# 18_DDR3_TOP.net
KiCad netlist of a schematic drawn in Altium Designer
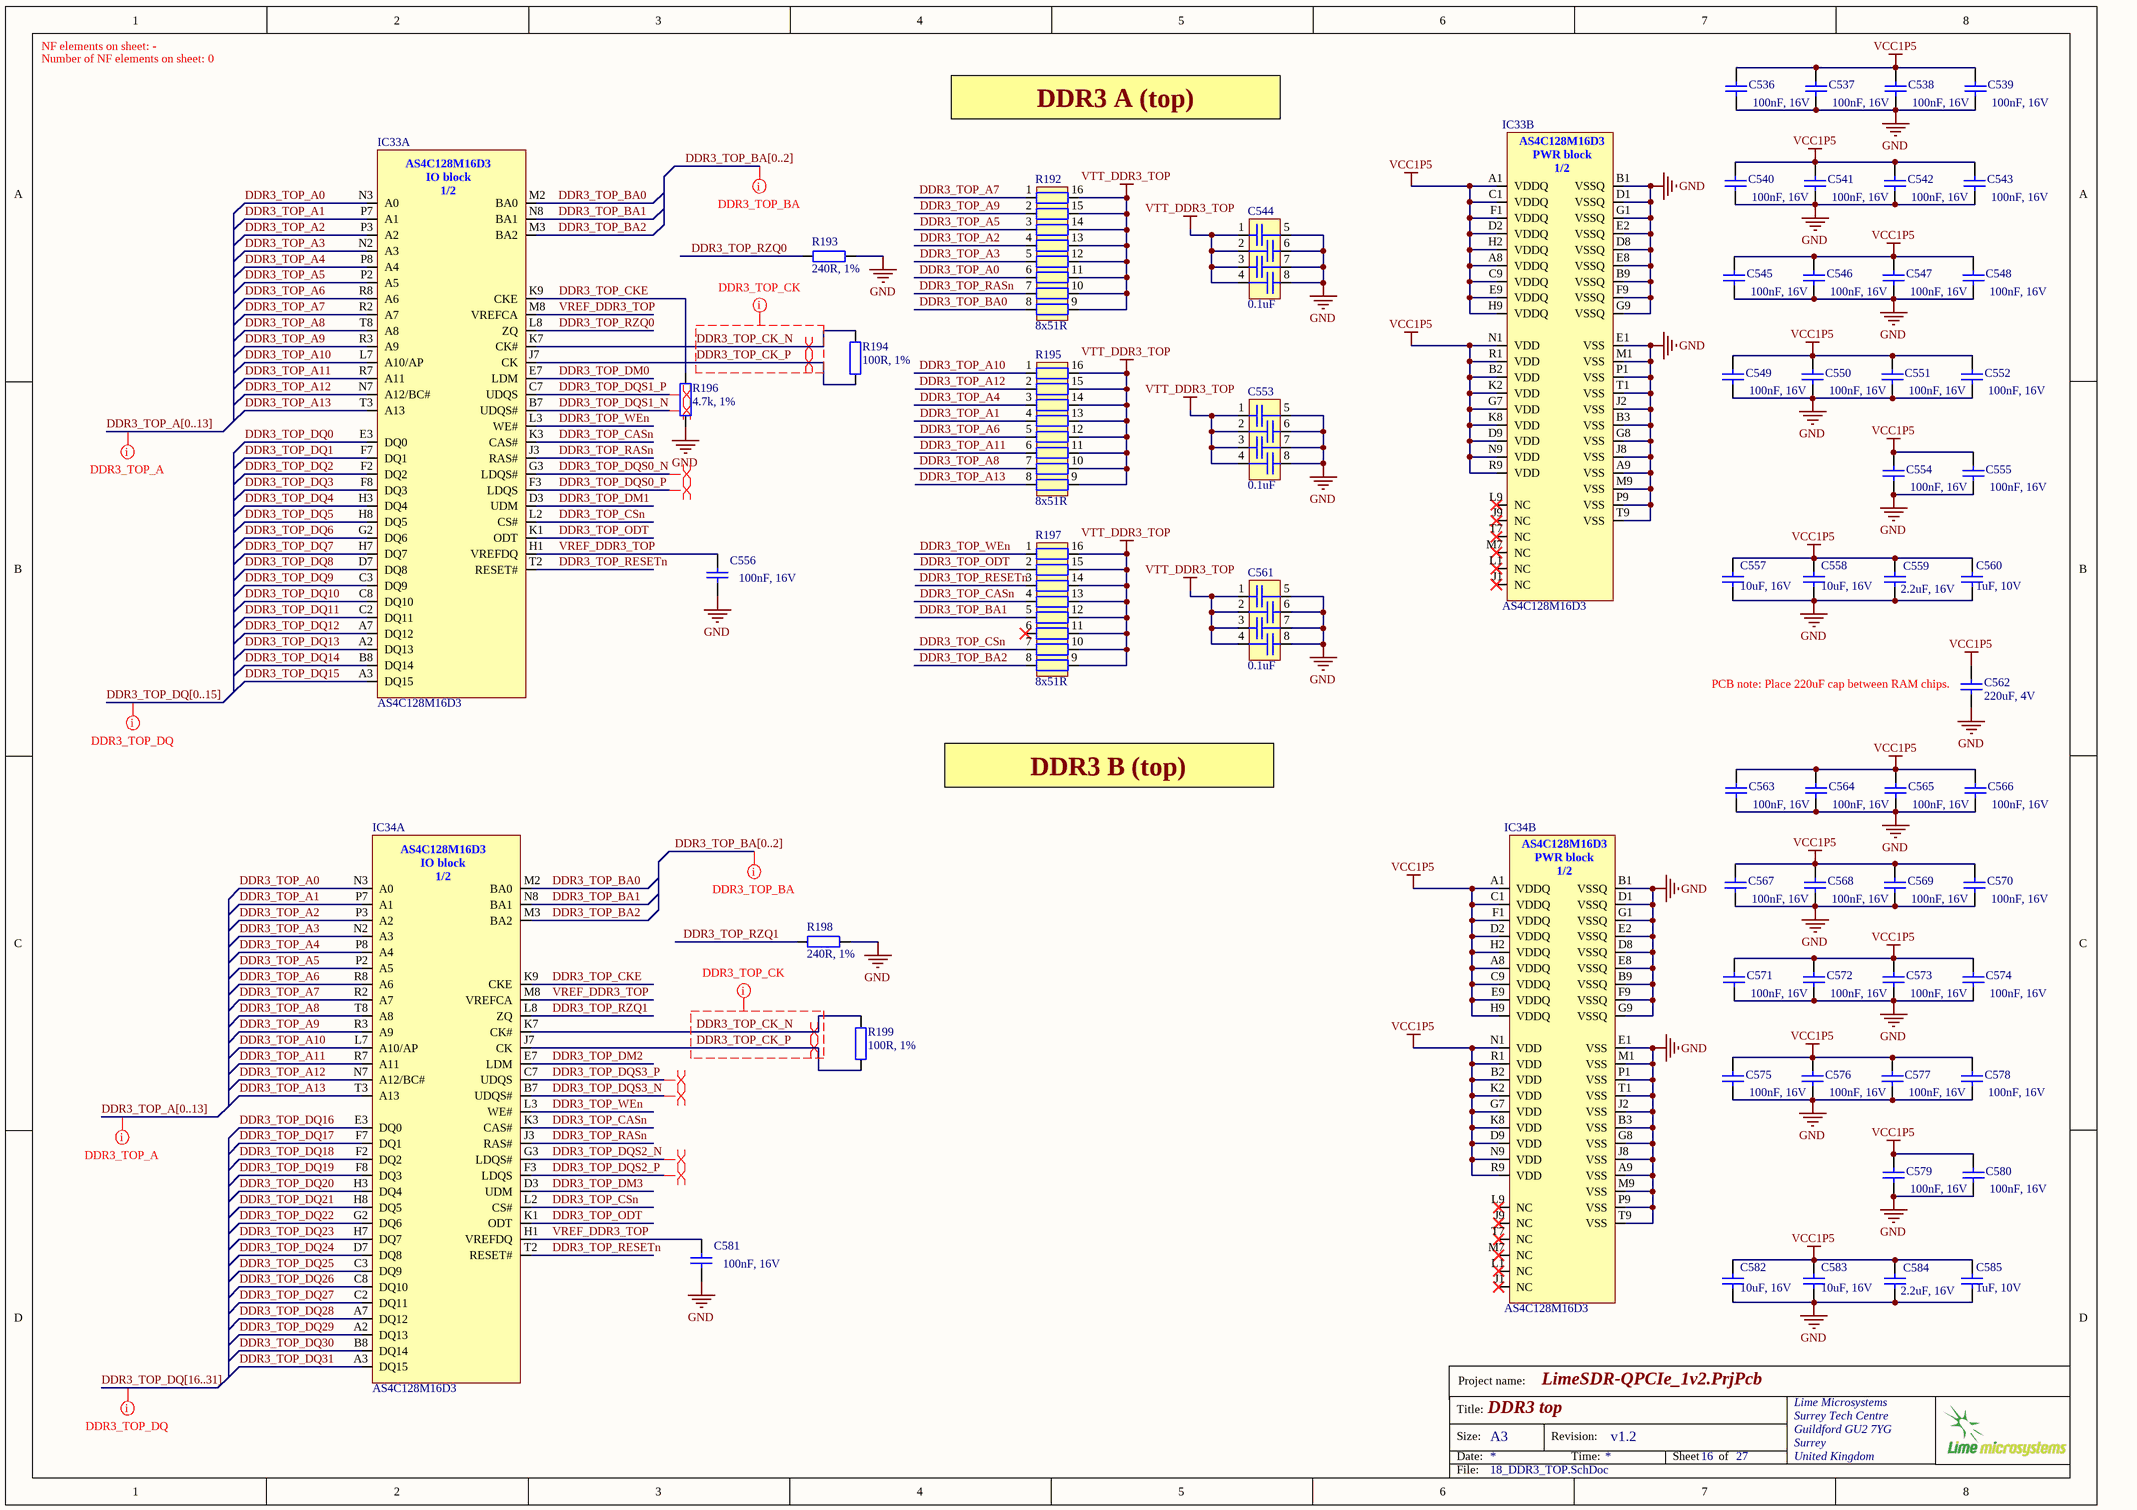
[diagram p0: 18_DDR3_TOP.SchDoc]

(export (version "E")
  (design (tool "Eeschema 10.0.6"))
  (components
    (comp (ref "C536")
      (value "100nF, 16V")
      (footprint "CAP0402")
      (fields
        (field (name "TOLERANCE") "10 %")
        (field (name "MANUFACTURER") "Murata Electronics")
        (field (name "MANUFACTURER PART NUMBER") "GRM155R71C104KA88D")
      )
      (libsource (lib "LimeFPGAboard_schLib") (part "Cap_0603"))
    )
    (comp (ref "C537")
      (value "100nF, 16V")
      (footprint "CAP0402")
      (fields
        (field (name "TOLERANCE") "10 %")
        (field (name "MANUFACTURER") "Murata Electronics")
        (field (name "MANUFACTURER PART NUMBER") "GRM155R71C104KA88D")
      )
      (libsource (lib "LimeFPGAboard_schLib") (part "Cap_0603"))
    )
    (comp (ref "C538")
      (value "100nF, 16V")
      (footprint "CAP0402")
      (fields
        (field (name "TOLERANCE") "10 %")
        (field (name "MANUFACTURER") "Murata Electronics")
        (field (name "MANUFACTURER PART NUMBER") "GRM155R71C104KA88D")
      )
      (libsource (lib "LimeFPGAboard_schLib") (part "Cap_0603"))
    )
    (comp (ref "C539")
      (value "100nF, 16V")
      (footprint "CAP0402")
      (fields
        (field (name "TOLERANCE") "10 %")
        (field (name "MANUFACTURER") "Murata Electronics")
        (field (name "MANUFACTURER PART NUMBER") "GRM155R71C104KA88D")
      )
      (libsource (lib "LimeFPGAboard_schLib") (part "Cap_0603"))
    )
    (comp (ref "C540")
      (value "100nF, 16V")
      (footprint "CAP0402")
      (fields
        (field (name "TOLERANCE") "10 %")
        (field (name "MANUFACTURER") "Murata Electronics")
        (field (name "MANUFACTURER PART NUMBER") "GRM155R71C104KA88D")
      )
      (libsource (lib "LimeFPGAboard_schLib") (part "Cap_0603"))
    )
    (comp (ref "C541")
      (value "100nF, 16V")
      (footprint "CAP0402")
      (fields
        (field (name "TOLERANCE") "10 %")
        (field (name "MANUFACTURER") "Murata Electronics")
        (field (name "MANUFACTURER PART NUMBER") "GRM155R71C104KA88D")
      )
      (libsource (lib "LimeFPGAboard_schLib") (part "Cap_0603"))
    )
    (comp (ref "C542")
      (value "100nF, 16V")
      (footprint "CAP0402")
      (fields
        (field (name "TOLERANCE") "10 %")
        (field (name "MANUFACTURER") "Murata Electronics")
        (field (name "MANUFACTURER PART NUMBER") "GRM155R71C104KA88D")
      )
      (libsource (lib "LimeFPGAboard_schLib") (part "Cap_0603"))
    )
    (comp (ref "C543")
      (value "100nF, 16V")
      (footprint "CAP0402")
      (fields
        (field (name "TOLERANCE") "10 %")
        (field (name "MANUFACTURER") "Murata Electronics")
        (field (name "MANUFACTURER PART NUMBER") "GRM155R71C104KA88D")
      )
      (libsource (lib "LimeFPGAboard_schLib") (part "Cap_0603"))
    )
    (comp (ref "C544")
      (value "0.1uF")
      (footprint "CKCA43X7R1C104M100AA")
      (fields (field (name "MANUFACTURER") "TDK") (field (name "TOLERANCE") "20 %"))
      (libsource (lib "LimeFPGAboard_schLib") (part "4X_cap_array_1206"))
    )
    (comp (ref "C545")
      (value "100nF, 16V")
      (footprint "CAP0402")
      (fields
        (field (name "TOLERANCE") "10 %")
        (field (name "MANUFACTURER") "Murata Electronics")
        (field (name "MANUFACTURER PART NUMBER") "GRM155R71C104KA88D")
      )
      (libsource (lib "LimeFPGAboard_schLib") (part "Cap_0603"))
    )
    (comp (ref "C546")
      (value "100nF, 16V")
      (footprint "CAP0402")
      (fields
        (field (name "TOLERANCE") "10 %")
        (field (name "MANUFACTURER") "Murata Electronics")
        (field (name "MANUFACTURER PART NUMBER") "GRM155R71C104KA88D")
      )
      (libsource (lib "LimeFPGAboard_schLib") (part "Cap_0603"))
    )
    (comp (ref "C547")
      (value "100nF, 16V")
      (footprint "CAP0402")
      (fields
        (field (name "TOLERANCE") "10 %")
        (field (name "MANUFACTURER") "Murata Electronics")
        (field (name "MANUFACTURER PART NUMBER") "GRM155R71C104KA88D")
      )
      (libsource (lib "LimeFPGAboard_schLib") (part "Cap_0603"))
    )
    (comp (ref "C548")
      (value "100nF, 16V")
      (footprint "CAP0402")
      (fields
        (field (name "TOLERANCE") "10 %")
        (field (name "MANUFACTURER") "Murata Electronics")
        (field (name "MANUFACTURER PART NUMBER") "GRM155R71C104KA88D")
      )
      (libsource (lib "LimeFPGAboard_schLib") (part "Cap_0603"))
    )
    (comp (ref "C549")
      (value "100nF, 16V")
      (footprint "CAP0402")
      (fields
        (field (name "TOLERANCE") "10 %")
        (field (name "MANUFACTURER") "Murata Electronics")
        (field (name "MANUFACTURER PART NUMBER") "GRM155R71C104KA88D")
      )
      (libsource (lib "LimeFPGAboard_schLib") (part "Cap_0603"))
    )
    (comp (ref "C550")
      (value "100nF, 16V")
      (footprint "CAP0402")
      (fields
        (field (name "TOLERANCE") "10 %")
        (field (name "MANUFACTURER") "Murata Electronics")
        (field (name "MANUFACTURER PART NUMBER") "GRM155R71C104KA88D")
      )
      (libsource (lib "LimeFPGAboard_schLib") (part "Cap_0603"))
    )
    (comp (ref "C551")
      (value "100nF, 16V")
      (footprint "CAP0402")
      (fields
        (field (name "TOLERANCE") "10 %")
        (field (name "MANUFACTURER") "Murata Electronics")
        (field (name "MANUFACTURER PART NUMBER") "GRM155R71C104KA88D")
      )
      (libsource (lib "LimeFPGAboard_schLib") (part "Cap_0603"))
    )
    (comp (ref "C552")
      (value "100nF, 16V")
      (footprint "CAP0402")
      (fields
        (field (name "TOLERANCE") "10 %")
        (field (name "MANUFACTURER") "Murata Electronics")
        (field (name "MANUFACTURER PART NUMBER") "GRM155R71C104KA88D")
      )
      (libsource (lib "LimeFPGAboard_schLib") (part "Cap_0603"))
    )
    (comp (ref "C553")
      (value "0.1uF")
      (footprint "CKCA43X7R1C104M100AA")
      (fields (field (name "MANUFACTURER") "TDK") (field (name "TOLERANCE") "20 %"))
      (libsource (lib "LimeFPGAboard_schLib") (part "4X_cap_array_1206"))
    )
    (comp (ref "C554")
      (value "100nF, 16V")
      (footprint "CAP0402")
      (fields
        (field (name "TOLERANCE") "10 %")
        (field (name "MANUFACTURER") "Murata Electronics")
        (field (name "MANUFACTURER PART NUMBER") "GRM155R71C104KA88D")
      )
      (libsource (lib "LimeFPGAboard_schLib") (part "Cap_0603"))
    )
    (comp (ref "C555")
      (value "100nF, 16V")
      (footprint "CAP0402")
      (fields
        (field (name "TOLERANCE") "10 %")
        (field (name "MANUFACTURER") "Murata Electronics")
        (field (name "MANUFACTURER PART NUMBER") "GRM155R71C104KA88D")
      )
      (libsource (lib "LimeFPGAboard_schLib") (part "Cap_0603"))
    )
    (comp (ref "C556")
      (value "100nF, 16V")
      (footprint "CAP0402")
      (fields
        (field (name "TOLERANCE") "10 %")
        (field (name "MANUFACTURER") "Murata Electronics")
        (field (name "MANUFACTURER PART NUMBER") "GRM155R71C104KA88D")
      )
      (libsource (lib "LimeFPGAboard_schLib") (part "Cap_0603"))
    )
    (comp (ref "C557")
      (value "10uF, 16V")
      (footprint "CAP0603")
      (fields (field (name "TOLERANCE") "±20%") (field (name "MANUFACTURER") "Yageo"))
      (libsource (lib "LimeFPGAboard_schLib") (part "Cap_0603"))
    )
    (comp (ref "C558")
      (value "10uF, 16V")
      (footprint "CAP0603")
      (fields (field (name "TOLERANCE") "±20%") (field (name "MANUFACTURER") "Yageo"))
      (libsource (lib "LimeFPGAboard_schLib") (part "Cap_0603"))
    )
    (comp (ref "C559")
      (value "2.2uF, 16V")
      (footprint "CAP0402")
      (description "CAP CER 2.2UF 16V 10% X5R 0402")
      (fields (field (name "TOLERANCE") "±10%") (field (name "MANUFACTURER") "TDK Corporation"))
      (libsource (lib "LimeFPGAboard_schLib") (part "Cap_0603"))
    )
    (comp (ref "C560")
      (value "1uF, 10V")
      (footprint "CAP0402")
      (fields (field (name "MANUFACTURER") "TDK"))
      (libsource (lib "LimeFPGAboard_schLib") (part "Cap_0603"))
    )
    (comp (ref "C561")
      (value "0.1uF")
      (footprint "CKCA43X7R1C104M100AA")
      (fields (field (name "MANUFACTURER") "TDK") (field (name "TOLERANCE") "20 %"))
      (libsource (lib "LimeFPGAboard_schLib") (part "4X_cap_array_1206"))
    )
    (comp (ref "C562")
      (value "220uF, 4V")
      (footprint "CAP1206")
      (fields
        (field (name "MANUFACTURER PART NUMBER") "GRM31CR60G227ME11L")
        (field (name "MANUFACTURER") "Murata Electronics North America")
        (field (name "TOLERANCE") "±20%")
      )
      (libsource (lib "LimeFPGAboard_schLib") (part "Cap_1206"))
    )
    (comp (ref "C563")
      (value "100nF, 16V")
      (footprint "CAP0402")
      (fields
        (field (name "TOLERANCE") "10 %")
        (field (name "MANUFACTURER") "Murata Electronics")
        (field (name "MANUFACTURER PART NUMBER") "GRM155R71C104KA88D")
      )
      (libsource (lib "LimeFPGAboard_schLib") (part "Cap_0603"))
    )
    (comp (ref "C564")
      (value "100nF, 16V")
      (footprint "CAP0402")
      (fields
        (field (name "TOLERANCE") "10 %")
        (field (name "MANUFACTURER") "Murata Electronics")
        (field (name "MANUFACTURER PART NUMBER") "GRM155R71C104KA88D")
      )
      (libsource (lib "LimeFPGAboard_schLib") (part "Cap_0603"))
    )
    (comp (ref "C565")
      (value "100nF, 16V")
      (footprint "CAP0402")
      (fields
        (field (name "TOLERANCE") "10 %")
        (field (name "MANUFACTURER") "Murata Electronics")
        (field (name "MANUFACTURER PART NUMBER") "GRM155R71C104KA88D")
      )
      (libsource (lib "LimeFPGAboard_schLib") (part "Cap_0603"))
    )
    (comp (ref "C566")
      (value "100nF, 16V")
      (footprint "CAP0402")
      (fields
        (field (name "TOLERANCE") "10 %")
        (field (name "MANUFACTURER") "Murata Electronics")
        (field (name "MANUFACTURER PART NUMBER") "GRM155R71C104KA88D")
      )
      (libsource (lib "LimeFPGAboard_schLib") (part "Cap_0603"))
    )
    (comp (ref "C567")
      (value "100nF, 16V")
      (footprint "CAP0402")
      (fields
        (field (name "TOLERANCE") "10 %")
        (field (name "MANUFACTURER") "Murata Electronics")
        (field (name "MANUFACTURER PART NUMBER") "GRM155R71C104KA88D")
      )
      (libsource (lib "LimeFPGAboard_schLib") (part "Cap_0603"))
    )
    (comp (ref "C568")
      (value "100nF, 16V")
      (footprint "CAP0402")
      (fields
        (field (name "TOLERANCE") "10 %")
        (field (name "MANUFACTURER") "Murata Electronics")
        (field (name "MANUFACTURER PART NUMBER") "GRM155R71C104KA88D")
      )
      (libsource (lib "LimeFPGAboard_schLib") (part "Cap_0603"))
    )
    (comp (ref "C569")
      (value "100nF, 16V")
      (footprint "CAP0402")
      (fields
        (field (name "TOLERANCE") "10 %")
        (field (name "MANUFACTURER") "Murata Electronics")
        (field (name "MANUFACTURER PART NUMBER") "GRM155R71C104KA88D")
      )
      (libsource (lib "LimeFPGAboard_schLib") (part "Cap_0603"))
    )
    (comp (ref "C570")
      (value "100nF, 16V")
      (footprint "CAP0402")
      (fields
        (field (name "TOLERANCE") "10 %")
        (field (name "MANUFACTURER") "Murata Electronics")
        (field (name "MANUFACTURER PART NUMBER") "GRM155R71C104KA88D")
      )
      (libsource (lib "LimeFPGAboard_schLib") (part "Cap_0603"))
    )
    (comp (ref "C571")
      (value "100nF, 16V")
      (footprint "CAP0402")
      (fields
        (field (name "TOLERANCE") "10 %")
        (field (name "MANUFACTURER") "Murata Electronics")
        (field (name "MANUFACTURER PART NUMBER") "GRM155R71C104KA88D")
      )
      (libsource (lib "LimeFPGAboard_schLib") (part "Cap_0603"))
    )
    (comp (ref "C572")
      (value "100nF, 16V")
      (footprint "CAP0402")
      (fields
        (field (name "TOLERANCE") "10 %")
        (field (name "MANUFACTURER") "Murata Electronics")
        (field (name "MANUFACTURER PART NUMBER") "GRM155R71C104KA88D")
      )
      (libsource (lib "LimeFPGAboard_schLib") (part "Cap_0603"))
    )
    (comp (ref "C573")
      (value "100nF, 16V")
      (footprint "CAP0402")
      (fields
        (field (name "TOLERANCE") "10 %")
        (field (name "MANUFACTURER") "Murata Electronics")
        (field (name "MANUFACTURER PART NUMBER") "GRM155R71C104KA88D")
      )
      (libsource (lib "LimeFPGAboard_schLib") (part "Cap_0603"))
    )
    (comp (ref "C574")
      (value "100nF, 16V")
      (footprint "CAP0402")
      (fields
        (field (name "TOLERANCE") "10 %")
        (field (name "MANUFACTURER") "Murata Electronics")
        (field (name "MANUFACTURER PART NUMBER") "GRM155R71C104KA88D")
      )
      (libsource (lib "LimeFPGAboard_schLib") (part "Cap_0603"))
    )
    (comp (ref "C575")
      (value "100nF, 16V")
      (footprint "CAP0402")
      (fields
        (field (name "TOLERANCE") "10 %")
        (field (name "MANUFACTURER") "Murata Electronics")
        (field (name "MANUFACTURER PART NUMBER") "GRM155R71C104KA88D")
      )
      (libsource (lib "LimeFPGAboard_schLib") (part "Cap_0603"))
    )
    (comp (ref "C576")
      (value "100nF, 16V")
      (footprint "CAP0402")
      (fields
        (field (name "TOLERANCE") "10 %")
        (field (name "MANUFACTURER") "Murata Electronics")
        (field (name "MANUFACTURER PART NUMBER") "GRM155R71C104KA88D")
      )
      (libsource (lib "LimeFPGAboard_schLib") (part "Cap_0603"))
    )
    (comp (ref "C577")
      (value "100nF, 16V")
      (footprint "CAP0402")
      (fields
        (field (name "TOLERANCE") "10 %")
        (field (name "MANUFACTURER") "Murata Electronics")
        (field (name "MANUFACTURER PART NUMBER") "GRM155R71C104KA88D")
      )
      (libsource (lib "LimeFPGAboard_schLib") (part "Cap_0603"))
    )
    (comp (ref "C578")
      (value "100nF, 16V")
      (footprint "CAP0402")
      (fields
        (field (name "TOLERANCE") "10 %")
        (field (name "MANUFACTURER") "Murata Electronics")
        (field (name "MANUFACTURER PART NUMBER") "GRM155R71C104KA88D")
      )
      (libsource (lib "LimeFPGAboard_schLib") (part "Cap_0603"))
    )
    (comp (ref "C579")
      (value "100nF, 16V")
      (footprint "CAP0402")
      (fields
        (field (name "TOLERANCE") "10 %")
        (field (name "MANUFACTURER") "Murata Electronics")
        (field (name "MANUFACTURER PART NUMBER") "GRM155R71C104KA88D")
      )
      (libsource (lib "LimeFPGAboard_schLib") (part "Cap_0603"))
    )
    (comp (ref "C580")
      (value "100nF, 16V")
      (footprint "CAP0402")
      (fields
        (field (name "TOLERANCE") "10 %")
        (field (name "MANUFACTURER") "Murata Electronics")
        (field (name "MANUFACTURER PART NUMBER") "GRM155R71C104KA88D")
      )
      (libsource (lib "LimeFPGAboard_schLib") (part "Cap_0603"))
    )
    (comp (ref "C581")
      (value "100nF, 16V")
      (footprint "CAP0402")
      (fields
        (field (name "TOLERANCE") "10 %")
        (field (name "MANUFACTURER") "Murata Electronics")
        (field (name "MANUFACTURER PART NUMBER") "GRM155R71C104KA88D")
      )
      (libsource (lib "LimeFPGAboard_schLib") (part "Cap_0603"))
    )
    (comp (ref "C582")
      (value "10uF, 16V")
      (footprint "CAP0603")
      (fields (field (name "TOLERANCE") "±20%") (field (name "MANUFACTURER") "Yageo"))
      (libsource (lib "LimeFPGAboard_schLib") (part "Cap_0603"))
    )
    (comp (ref "C583")
      (value "10uF, 16V")
      (footprint "CAP0603")
      (fields (field (name "TOLERANCE") "±20%") (field (name "MANUFACTURER") "Yageo"))
      (libsource (lib "LimeFPGAboard_schLib") (part "Cap_0603"))
    )
    (comp (ref "C584")
      (value "2.2uF, 16V")
      (footprint "CAP0402")
      (description "CAP CER 2.2UF 16V 10% X5R 0402")
      (fields (field (name "TOLERANCE") "±10%") (field (name "MANUFACTURER") "TDK Corporation"))
      (libsource (lib "LimeFPGAboard_schLib") (part "Cap_0603"))
    )
    (comp (ref "C585")
      (value "1uF, 10V")
      (footprint "CAP0402")
      (fields (field (name "MANUFACTURER") "TDK"))
      (libsource (lib "LimeFPGAboard_schLib") (part "Cap_0603"))
    )
    (comp (ref "IC33")
      (value "AS4C128M16D3")
      (footprint "AS4C128M16D3")
      (fields (field (name "MANUFACTURER") "Alliance Memory, Inc."))
      (libsource (lib "LimeFPGAboard_schLib") (part "AS4C128M16D3"))
    )
    (comp (ref "IC34")
      (value "AS4C128M16D3")
      (footprint "AS4C128M16D3")
      (fields (field (name "MANUFACTURER") "Alliance Memory, Inc."))
      (libsource (lib "LimeFPGAboard_schLib") (part "AS4C128M16D3"))
    )
    (comp (ref "R192")
      (value "8x51R")
      (footprint "EXB2HV")
      (fields
        (field (name "MANUFACTURER") "PANASONIC ELECTRONIC COMPONENTS")
        (field (name "MANUFACTURER_1") "Panasonic Electronic Components")
      )
      (libsource (lib "LimeFPGAboard_schLib") (part "8X_resistor_array_0402"))
    )
    (comp (ref "R193")
      (value "240R, 1%")
      (footprint "RES0402")
      (fields (field (name "TOLERANCE") "±1%") (field (name "MANUFACTURER") "Vishay Dale"))
      (libsource (lib "LimeFPGAboard_schLib") (part "Res_0402"))
    )
    (comp (ref "R194")
      (value "100R, 1%")
      (footprint "RES0402")
      (fields (field (name "TOLERANCE") "±1%") (field (name "MANUFACTURER") "Stackpole Electronics Inc."))
      (libsource (lib "LimeFPGAboard_schLib") (part "Res_0402"))
    )
    (comp (ref "R195")
      (value "8x51R")
      (footprint "EXB2HV")
      (fields
        (field (name "MANUFACTURER") "PANASONIC ELECTRONIC COMPONENTS")
        (field (name "MANUFACTURER_1") "Panasonic Electronic Components")
      )
      (libsource (lib "LimeFPGAboard_schLib") (part "8X_resistor_array_0402"))
    )
    (comp (ref "R196")
      (value "4.7k, 1%")
      (footprint "RES0402")
      (fields (field (name "MANUFACTURER") "Yageo") (field (name "TOLERANCE") "±1%"))
      (libsource (lib "LimeMicroAltiumLib_schLib") (part "Res_0402"))
    )
    (comp (ref "R197")
      (value "8x51R")
      (footprint "EXB2HV")
      (fields
        (field (name "MANUFACTURER") "PANASONIC ELECTRONIC COMPONENTS")
        (field (name "MANUFACTURER_1") "Panasonic Electronic Components")
      )
      (libsource (lib "LimeFPGAboard_schLib") (part "8X_resistor_array_0402"))
    )
    (comp (ref "R198")
      (value "240R, 1%")
      (footprint "RES0402")
      (fields (field (name "TOLERANCE") "±1%") (field (name "MANUFACTURER") "Vishay Dale"))
      (libsource (lib "LimeFPGAboard_schLib") (part "Res_0402"))
    )
    (comp (ref "R199")
      (value "100R, 1%")
      (footprint "RES0402")
      (fields (field (name "TOLERANCE") "±1%") (field (name "MANUFACTURER") "Stackpole Electronics Inc."))
      (libsource (lib "LimeFPGAboard_schLib") (part "Res_0402"))
    )
  )
  (nets
    (net (code "1") (name "/DDR3_TOP_A0") (class "Default")
      (node (ref "IC33") (pin "N3") (pinfunction "A0_N3") (pintype "passive"))
      (node (ref "IC34") (pin "N3") (pinfunction "A0_N3") (pintype "passive"))
      (node (ref "R192") (pin "6") (pinfunction "6_6") (pintype "passive"))
    )
    (net (code "2") (name "/DDR3_TOP_A1") (class "Default")
      (node (ref "IC33") (pin "P7") (pinfunction "A1_P7") (pintype "passive"))
      (node (ref "IC34") (pin "P7") (pinfunction "A1_P7") (pintype "passive"))
      (node (ref "R195") (pin "4") (pinfunction "4_4") (pintype "passive"))
    )
    (net (code "3") (name "/DDR3_TOP_A2") (class "Default")
      (node (ref "IC33") (pin "P3") (pinfunction "A2_P3") (pintype "passive"))
      (node (ref "IC34") (pin "P3") (pinfunction "A2_P3") (pintype "passive"))
      (node (ref "R192") (pin "4") (pinfunction "4_4") (pintype "passive"))
    )
    (net (code "4") (name "/DDR3_TOP_A3") (class "Default")
      (node (ref "IC33") (pin "N2") (pinfunction "A3_N2") (pintype "passive"))
      (node (ref "IC34") (pin "N2") (pinfunction "A3_N2") (pintype "passive"))
      (node (ref "R192") (pin "5") (pinfunction "5_5") (pintype "passive"))
    )
    (net (code "5") (name "/DDR3_TOP_A4") (class "Default")
      (node (ref "IC33") (pin "P8") (pinfunction "A4_P8") (pintype "passive"))
      (node (ref "IC34") (pin "P8") (pinfunction "A4_P8") (pintype "passive"))
      (node (ref "R195") (pin "3") (pinfunction "3_3") (pintype "passive"))
    )
    (net (code "6") (name "/DDR3_TOP_A5") (class "Default")
      (node (ref "IC33") (pin "P2") (pinfunction "A5_P2") (pintype "passive"))
      (node (ref "IC34") (pin "P2") (pinfunction "A5_P2") (pintype "passive"))
      (node (ref "R192") (pin "3") (pinfunction "3_3") (pintype "passive"))
    )
    (net (code "7") (name "/DDR3_TOP_A6") (class "Default")
      (node (ref "IC33") (pin "R8") (pinfunction "A6_R8") (pintype "passive"))
      (node (ref "IC34") (pin "R8") (pinfunction "A6_R8") (pintype "passive"))
      (node (ref "R195") (pin "5") (pinfunction "5_5") (pintype "passive"))
    )
    (net (code "8") (name "/DDR3_TOP_A7") (class "Default")
      (node (ref "IC33") (pin "R2") (pinfunction "A7_R2") (pintype "passive"))
      (node (ref "IC34") (pin "R2") (pinfunction "A7_R2") (pintype "passive"))
      (node (ref "R192") (pin "1") (pinfunction "1_1") (pintype "passive"))
    )
    (net (code "9") (name "/DDR3_TOP_A8") (class "Default")
      (node (ref "IC33") (pin "T8") (pinfunction "A8_T8") (pintype "passive"))
      (node (ref "IC34") (pin "T8") (pinfunction "A8_T8") (pintype "passive"))
      (node (ref "R195") (pin "7") (pinfunction "7_7") (pintype "passive"))
    )
    (net (code "10") (name "/DDR3_TOP_A9") (class "Default")
      (node (ref "IC33") (pin "R3") (pinfunction "A9_R3") (pintype "passive"))
      (node (ref "IC34") (pin "R3") (pinfunction "A9_R3") (pintype "passive"))
      (node (ref "R192") (pin "2") (pinfunction "2_2") (pintype "passive"))
    )
    (net (code "11") (name "/DDR3_TOP_A10") (class "Default")
      (node (ref "IC33") (pin "L7") (pinfunction "A10/AP_L7") (pintype "passive"))
      (node (ref "IC34") (pin "L7") (pinfunction "A10/AP_L7") (pintype "passive"))
      (node (ref "R195") (pin "1") (pinfunction "1_1") (pintype "passive"))
    )
    (net (code "12") (name "/DDR3_TOP_A11") (class "Default")
      (node (ref "IC33") (pin "R7") (pinfunction "A11_R7") (pintype "passive"))
      (node (ref "IC34") (pin "R7") (pinfunction "A11_R7") (pintype "passive"))
      (node (ref "R195") (pin "6") (pinfunction "6_6") (pintype "passive"))
    )
    (net (code "13") (name "/DDR3_TOP_A12") (class "Default")
      (node (ref "IC33") (pin "N7") (pinfunction "A12/BC#_N7") (pintype "passive"))
      (node (ref "IC34") (pin "N7") (pinfunction "A12/BC#_N7") (pintype "passive"))
      (node (ref "R195") (pin "2") (pinfunction "2_2") (pintype "passive"))
    )
    (net (code "14") (name "/DDR3_TOP_A13") (class "Default")
      (node (ref "IC33") (pin "T3") (pinfunction "A13_T3") (pintype "passive"))
      (node (ref "IC34") (pin "T3") (pinfunction "A13_T3") (pintype "passive"))
      (node (ref "R195") (pin "8") (pinfunction "8_8") (pintype "passive"))
    )
    (net (code "16") (name "/DDR3_TOP_BA0") (class "Default")
      (node (ref "IC33") (pin "M2") (pinfunction "BA0_M2") (pintype "passive"))
      (node (ref "IC34") (pin "M2") (pinfunction "BA0_M2") (pintype "passive"))
      (node (ref "R192") (pin "8") (pinfunction "8_8") (pintype "passive"))
    )
    (net (code "17") (name "/DDR3_TOP_BA1") (class "Default")
      (node (ref "IC33") (pin "N8") (pinfunction "BA1_N8") (pintype "passive"))
      (node (ref "IC34") (pin "N8") (pinfunction "BA1_N8") (pintype "passive"))
      (node (ref "R197") (pin "5") (pinfunction "5_5") (pintype "passive"))
    )
    (net (code "18") (name "/DDR3_TOP_BA2") (class "Default")
      (node (ref "IC33") (pin "M3") (pinfunction "BA2_M3") (pintype "passive"))
      (node (ref "IC34") (pin "M3") (pinfunction "BA2_M3") (pintype "passive"))
      (node (ref "R197") (pin "8") (pinfunction "8_8") (pintype "passive"))
    )
    (net (code "20") (name "/DDR3_TOP_CASn") (class "Default")
      (node (ref "IC33") (pin "K3") (pinfunction "CAS#_K3") (pintype "passive"))
      (node (ref "IC34") (pin "K3") (pinfunction "CAS#_K3") (pintype "passive"))
      (node (ref "R197") (pin "4") (pinfunction "4_4") (pintype "passive"))
    )
    (net (code "21") (name "/DDR3_TOP_CKE") (class "Default")
      (node (ref "IC33") (pin "K9") (pinfunction "CKE_K9") (pintype "passive"))
      (node (ref "IC34") (pin "K9") (pinfunction "CKE_K9") (pintype "passive"))
      (node (ref "R196") (pin "1") (pinfunction "1_1") (pintype "passive"))
    )
    (net (code "22") (name "/DDR3_TOP_CK_N") (class "Default")
      (node (ref "IC33") (pin "K7") (pinfunction "CK#_K7") (pintype "passive"))
      (node (ref "IC34") (pin "K7") (pinfunction "CK#_K7") (pintype "passive"))
      (node (ref "R194") (pin "2") (pinfunction "2_2") (pintype "passive"))
      (node (ref "R199") (pin "2") (pinfunction "2_2") (pintype "passive"))
    )
    (net (code "23") (name "/DDR3_TOP_CK_P") (class "Default")
      (node (ref "IC33") (pin "J7") (pinfunction "CK_J7") (pintype "passive"))
      (node (ref "IC34") (pin "J7") (pinfunction "CK_J7") (pintype "passive"))
      (node (ref "R194") (pin "1") (pinfunction "1_1") (pintype "passive"))
      (node (ref "R199") (pin "1") (pinfunction "1_1") (pintype "passive"))
    )
    (net (code "24") (name "/DDR3_TOP_CSn") (class "Default")
      (node (ref "IC33") (pin "L2") (pinfunction "CS#_L2") (pintype "passive"))
      (node (ref "IC34") (pin "L2") (pinfunction "CS#_L2") (pintype "passive"))
      (node (ref "R197") (pin "7") (pinfunction "7_7") (pintype "passive"))
    )
    (net (code "25") (name "/DDR3_TOP_DM0") (class "Default")
      (node (ref "IC33") (pin "E7") (pinfunction "LDM_E7") (pintype "passive"))
    )
    (net (code "26") (name "/DDR3_TOP_DM1") (class "Default")
      (node (ref "IC33") (pin "D3") (pinfunction "UDM_D3") (pintype "passive"))
    )
    (net (code "27") (name "/DDR3_TOP_DM2") (class "Default")
      (node (ref "IC34") (pin "E7") (pinfunction "LDM_E7") (pintype "passive"))
    )
    (net (code "28") (name "/DDR3_TOP_DM3") (class "Default")
      (node (ref "IC34") (pin "D3") (pinfunction "UDM_D3") (pintype "passive"))
    )
    (net (code "29") (name "/DDR3_TOP_DQ0") (class "Default")
      (node (ref "IC33") (pin "E3") (pinfunction "DQ0_E3") (pintype "passive"))
    )
    (net (code "30") (name "/DDR3_TOP_DQ1") (class "Default")
      (node (ref "IC33") (pin "F7") (pinfunction "DQ1_F7") (pintype "passive"))
    )
    (net (code "31") (name "/DDR3_TOP_DQ2") (class "Default")
      (node (ref "IC33") (pin "F2") (pinfunction "DQ2_F2") (pintype "passive"))
    )
    (net (code "32") (name "/DDR3_TOP_DQ3") (class "Default")
      (node (ref "IC33") (pin "F8") (pinfunction "DQ3_F8") (pintype "passive"))
    )
    (net (code "33") (name "/DDR3_TOP_DQ4") (class "Default")
      (node (ref "IC33") (pin "H3") (pinfunction "DQ4_H3") (pintype "passive"))
    )
    (net (code "34") (name "/DDR3_TOP_DQ5") (class "Default")
      (node (ref "IC33") (pin "H8") (pinfunction "DQ5_H8") (pintype "passive"))
    )
    (net (code "35") (name "/DDR3_TOP_DQ6") (class "Default")
      (node (ref "IC33") (pin "G2") (pinfunction "DQ6_G2") (pintype "passive"))
    )
    (net (code "36") (name "/DDR3_TOP_DQ7") (class "Default")
      (node (ref "IC33") (pin "H7") (pinfunction "DQ7_H7") (pintype "passive"))
    )
    (net (code "37") (name "/DDR3_TOP_DQ8") (class "Default")
      (node (ref "IC33") (pin "D7") (pinfunction "DQ8_D7") (pintype "passive"))
    )
    (net (code "38") (name "/DDR3_TOP_DQ9") (class "Default")
      (node (ref "IC33") (pin "C3") (pinfunction "DQ9_C3") (pintype "passive"))
    )
    (net (code "39") (name "/DDR3_TOP_DQ10") (class "Default")
      (node (ref "IC33") (pin "C8") (pinfunction "DQ10_C8") (pintype "passive"))
    )
    (net (code "40") (name "/DDR3_TOP_DQ11") (class "Default")
      (node (ref "IC33") (pin "C2") (pinfunction "DQ11_C2") (pintype "passive"))
    )
    (net (code "41") (name "/DDR3_TOP_DQ12") (class "Default")
      (node (ref "IC33") (pin "A7") (pinfunction "DQ12_A7") (pintype "passive"))
    )
    (net (code "42") (name "/DDR3_TOP_DQ13") (class "Default")
      (node (ref "IC33") (pin "A2") (pinfunction "DQ13_A2") (pintype "passive"))
    )
    (net (code "43") (name "/DDR3_TOP_DQ14") (class "Default")
      (node (ref "IC33") (pin "B8") (pinfunction "DQ14_B8") (pintype "passive"))
    )
    (net (code "44") (name "/DDR3_TOP_DQ15") (class "Default")
      (node (ref "IC33") (pin "A3") (pinfunction "DQ15_A3") (pintype "passive"))
    )
    (net (code "45") (name "/DDR3_TOP_DQ16") (class "Default")
      (node (ref "IC34") (pin "E3") (pinfunction "DQ0_E3") (pintype "passive"))
    )
    (net (code "46") (name "/DDR3_TOP_DQ17") (class "Default")
      (node (ref "IC34") (pin "F7") (pinfunction "DQ1_F7") (pintype "passive"))
    )
    (net (code "47") (name "/DDR3_TOP_DQ18") (class "Default")
      (node (ref "IC34") (pin "F2") (pinfunction "DQ2_F2") (pintype "passive"))
    )
    (net (code "48") (name "/DDR3_TOP_DQ19") (class "Default")
      (node (ref "IC34") (pin "F8") (pinfunction "DQ3_F8") (pintype "passive"))
    )
    (net (code "49") (name "/DDR3_TOP_DQ20") (class "Default")
      (node (ref "IC34") (pin "H3") (pinfunction "DQ4_H3") (pintype "passive"))
    )
    (net (code "50") (name "/DDR3_TOP_DQ21") (class "Default")
      (node (ref "IC34") (pin "H8") (pinfunction "DQ5_H8") (pintype "passive"))
    )
    (net (code "51") (name "/DDR3_TOP_DQ22") (class "Default")
      (node (ref "IC34") (pin "G2") (pinfunction "DQ6_G2") (pintype "passive"))
    )
    (net (code "52") (name "/DDR3_TOP_DQ23") (class "Default")
      (node (ref "IC34") (pin "H7") (pinfunction "DQ7_H7") (pintype "passive"))
    )
    (net (code "53") (name "/DDR3_TOP_DQ24") (class "Default")
      (node (ref "IC34") (pin "D7") (pinfunction "DQ8_D7") (pintype "passive"))
    )
    (net (code "54") (name "/DDR3_TOP_DQ25") (class "Default")
      (node (ref "IC34") (pin "C3") (pinfunction "DQ9_C3") (pintype "passive"))
    )
    (net (code "55") (name "/DDR3_TOP_DQ26") (class "Default")
      (node (ref "IC34") (pin "C8") (pinfunction "DQ10_C8") (pintype "passive"))
    )
    (net (code "56") (name "/DDR3_TOP_DQ27") (class "Default")
      (node (ref "IC34") (pin "C2") (pinfunction "DQ11_C2") (pintype "passive"))
    )
    (net (code "57") (name "/DDR3_TOP_DQ28") (class "Default")
      (node (ref "IC34") (pin "A7") (pinfunction "DQ12_A7") (pintype "passive"))
    )
    (net (code "58") (name "/DDR3_TOP_DQ29") (class "Default")
      (node (ref "IC34") (pin "A2") (pinfunction "DQ13_A2") (pintype "passive"))
    )
    (net (code "59") (name "/DDR3_TOP_DQ30") (class "Default")
      (node (ref "IC34") (pin "B8") (pinfunction "DQ14_B8") (pintype "passive"))
    )
    (net (code "60") (name "/DDR3_TOP_DQ31") (class "Default")
      (node (ref "IC34") (pin "A3") (pinfunction "DQ15_A3") (pintype "passive"))
    )
    (net (code "61") (name "/DDR3_TOP_DQS0_N") (class "Default")
      (node (ref "IC33") (pin "G3") (pinfunction "LDQS#_G3") (pintype "passive"))
    )
    (net (code "62") (name "/DDR3_TOP_DQS0_P") (class "Default")
      (node (ref "IC33") (pin "F3") (pinfunction "LDQS_F3") (pintype "passive"))
    )
    (net (code "63") (name "/DDR3_TOP_DQS1_N") (class "Default")
      (node (ref "IC33") (pin "B7") (pinfunction "UDQS#_B7") (pintype "passive"))
    )
    (net (code "64") (name "/DDR3_TOP_DQS1_P") (class "Default")
      (node (ref "IC33") (pin "C7") (pinfunction "UDQS_C7") (pintype "passive"))
    )
    (net (code "65") (name "/DDR3_TOP_DQS2_N") (class "Default")
      (node (ref "IC34") (pin "G3") (pinfunction "LDQS#_G3") (pintype "passive"))
    )
    (net (code "66") (name "/DDR3_TOP_DQS2_P") (class "Default")
      (node (ref "IC34") (pin "F3") (pinfunction "LDQS_F3") (pintype "passive"))
    )
    (net (code "67") (name "/DDR3_TOP_DQS3_N") (class "Default")
      (node (ref "IC34") (pin "B7") (pinfunction "UDQS#_B7") (pintype "passive"))
    )
    (net (code "68") (name "/DDR3_TOP_DQS3_P") (class "Default")
      (node (ref "IC34") (pin "C7") (pinfunction "UDQS_C7") (pintype "passive"))
    )
    (net (code "71") (name "/DDR3_TOP_ODT") (class "Default")
      (node (ref "IC33") (pin "K1") (pinfunction "ODT_K1") (pintype "passive"))
      (node (ref "IC34") (pin "K1") (pinfunction "ODT_K1") (pintype "passive"))
      (node (ref "R197") (pin "2") (pinfunction "2_2") (pintype "passive"))
    )
    (net (code "72") (name "/DDR3_TOP_RASn") (class "Default")
      (node (ref "IC33") (pin "J3") (pinfunction "RAS#_J3") (pintype "passive"))
      (node (ref "IC34") (pin "J3") (pinfunction "RAS#_J3") (pintype "passive"))
      (node (ref "R192") (pin "7") (pinfunction "7_7") (pintype "passive"))
    )
    (net (code "73") (name "/DDR3_TOP_RESETn") (class "Default")
      (node (ref "IC33") (pin "T2") (pinfunction "RESET#_T2") (pintype "passive"))
      (node (ref "IC34") (pin "T2") (pinfunction "RESET#_T2") (pintype "passive"))
      (node (ref "R197") (pin "3") (pinfunction "3_3") (pintype "passive"))
    )
    (net (code "74") (name "/DDR3_TOP_RZQ0") (class "Default")
      (node (ref "IC33") (pin "L8") (pinfunction "ZQ_L8") (pintype "passive"))
      (node (ref "R193") (pin "1") (pinfunction "1_1") (pintype "passive"))
    )
    (net (code "75") (name "/DDR3_TOP_RZQ1") (class "Default")
      (node (ref "IC34") (pin "L8") (pinfunction "ZQ_L8") (pintype "passive"))
      (node (ref "R198") (pin "1") (pinfunction "1_1") (pintype "passive"))
    )
    (net (code "76") (name "/DDR3_TOP_WEn") (class "Default")
      (node (ref "IC33") (pin "L3") (pinfunction "WE#_L3") (pintype "passive"))
      (node (ref "IC34") (pin "L3") (pinfunction "WE#_L3") (pintype "passive"))
      (node (ref "R197") (pin "1") (pinfunction "1_1") (pintype "passive"))
    )
    (net (code "77") (name "/VREF_DDR3_TOP") (class "Default")
      (node (ref "C556") (pin "1") (pinfunction "1_1") (pintype "passive"))
      (node (ref "C581") (pin "1") (pinfunction "1_1") (pintype "passive"))
      (node (ref "IC33") (pin "H1") (pinfunction "VREFDQ_H1") (pintype "passive"))
      (node (ref "IC33") (pin "M8") (pinfunction "VREFCA_M8") (pintype "passive"))
      (node (ref "IC34") (pin "H1") (pinfunction "VREFDQ_H1") (pintype "passive"))
      (node (ref "IC34") (pin "M8") (pinfunction "VREFCA_M8") (pintype "passive"))
    )
    (net (code "78") (name "GND") (class "Default")
      (node (ref "C536") (pin "2") (pinfunction "2_2") (pintype "passive"))
      (node (ref "C537") (pin "2") (pinfunction "2_2") (pintype "passive"))
      (node (ref "C538") (pin "2") (pinfunction "2_2") (pintype "passive"))
      (node (ref "C539") (pin "2") (pinfunction "2_2") (pintype "passive"))
      (node (ref "C540") (pin "2") (pinfunction "2_2") (pintype "passive"))
      (node (ref "C541") (pin "2") (pinfunction "2_2") (pintype "passive"))
      (node (ref "C542") (pin "2") (pinfunction "2_2") (pintype "passive"))
      (node (ref "C543") (pin "2") (pinfunction "2_2") (pintype "passive"))
      (node (ref "C544") (pin "5") (pinfunction "5_5") (pintype "passive"))
      (node (ref "C544") (pin "6") (pinfunction "6_6") (pintype "passive"))
      (node (ref "C544") (pin "7") (pinfunction "7_7") (pintype "passive"))
      (node (ref "C544") (pin "8") (pinfunction "8_8") (pintype "passive"))
      (node (ref "C545") (pin "2") (pinfunction "2_2") (pintype "passive"))
      (node (ref "C546") (pin "2") (pinfunction "2_2") (pintype "passive"))
      (node (ref "C547") (pin "2") (pinfunction "2_2") (pintype "passive"))
      (node (ref "C548") (pin "2") (pinfunction "2_2") (pintype "passive"))
      (node (ref "C549") (pin "2") (pinfunction "2_2") (pintype "passive"))
      (node (ref "C550") (pin "2") (pinfunction "2_2") (pintype "passive"))
      (node (ref "C551") (pin "2") (pinfunction "2_2") (pintype "passive"))
      (node (ref "C552") (pin "2") (pinfunction "2_2") (pintype "passive"))
      (node (ref "C553") (pin "5") (pinfunction "5_5") (pintype "passive"))
      (node (ref "C553") (pin "6") (pinfunction "6_6") (pintype "passive"))
      (node (ref "C553") (pin "7") (pinfunction "7_7") (pintype "passive"))
      (node (ref "C553") (pin "8") (pinfunction "8_8") (pintype "passive"))
      (node (ref "C554") (pin "2") (pinfunction "2_2") (pintype "passive"))
      (node (ref "C555") (pin "2") (pinfunction "2_2") (pintype "passive"))
      (node (ref "C556") (pin "2") (pinfunction "2_2") (pintype "passive"))
      (node (ref "C557") (pin "1") (pinfunction "1_1") (pintype "passive"))
      (node (ref "C558") (pin "1") (pinfunction "1_1") (pintype "passive"))
      (node (ref "C559") (pin "2") (pinfunction "2_2") (pintype "passive"))
      (node (ref "C560") (pin "1") (pinfunction "1_1") (pintype "passive"))
      (node (ref "C561") (pin "5") (pinfunction "5_5") (pintype "passive"))
      (node (ref "C561") (pin "6") (pinfunction "6_6") (pintype "passive"))
      (node (ref "C561") (pin "7") (pinfunction "7_7") (pintype "passive"))
      (node (ref "C561") (pin "8") (pinfunction "8_8") (pintype "passive"))
      (node (ref "C562") (pin "1") (pinfunction "1_1") (pintype "passive"))
      (node (ref "C563") (pin "2") (pinfunction "2_2") (pintype "passive"))
      (node (ref "C564") (pin "2") (pinfunction "2_2") (pintype "passive"))
      (node (ref "C565") (pin "2") (pinfunction "2_2") (pintype "passive"))
      (node (ref "C566") (pin "2") (pinfunction "2_2") (pintype "passive"))
      (node (ref "C567") (pin "2") (pinfunction "2_2") (pintype "passive"))
      (node (ref "C568") (pin "2") (pinfunction "2_2") (pintype "passive"))
      (node (ref "C569") (pin "2") (pinfunction "2_2") (pintype "passive"))
      (node (ref "C570") (pin "2") (pinfunction "2_2") (pintype "passive"))
      (node (ref "C571") (pin "2") (pinfunction "2_2") (pintype "passive"))
      (node (ref "C572") (pin "2") (pinfunction "2_2") (pintype "passive"))
      (node (ref "C573") (pin "2") (pinfunction "2_2") (pintype "passive"))
      (node (ref "C574") (pin "2") (pinfunction "2_2") (pintype "passive"))
      (node (ref "C575") (pin "2") (pinfunction "2_2") (pintype "passive"))
      (node (ref "C576") (pin "2") (pinfunction "2_2") (pintype "passive"))
      (node (ref "C577") (pin "2") (pinfunction "2_2") (pintype "passive"))
      (node (ref "C578") (pin "2") (pinfunction "2_2") (pintype "passive"))
      (node (ref "C579") (pin "2") (pinfunction "2_2") (pintype "passive"))
      (node (ref "C580") (pin "2") (pinfunction "2_2") (pintype "passive"))
      (node (ref "C581") (pin "2") (pinfunction "2_2") (pintype "passive"))
      (node (ref "C582") (pin "1") (pinfunction "1_1") (pintype "passive"))
      (node (ref "C583") (pin "1") (pinfunction "1_1") (pintype "passive"))
      (node (ref "C584") (pin "2") (pinfunction "2_2") (pintype "passive"))
      (node (ref "C585") (pin "1") (pinfunction "1_1") (pintype "passive"))
      (node (ref "IC33") (pin "A9") (pinfunction "VSS_A9") (pintype "power_in"))
      (node (ref "IC33") (pin "B1") (pinfunction "VSSQ_B1") (pintype "power_in"))
      (node (ref "IC33") (pin "B3") (pinfunction "VSS_B3") (pintype "power_in"))
      (node (ref "IC33") (pin "B9") (pinfunction "VSSQ_B9") (pintype "power_in"))
      (node (ref "IC33") (pin "D1") (pinfunction "VSSQ_D1") (pintype "power_in"))
      (node (ref "IC33") (pin "D8") (pinfunction "VSSQ_D8") (pintype "power_in"))
      (node (ref "IC33") (pin "E1") (pinfunction "VSS_E1") (pintype "power_in"))
      (node (ref "IC33") (pin "E2") (pinfunction "VSSQ_E2") (pintype "power_in"))
      (node (ref "IC33") (pin "E8") (pinfunction "VSSQ_E8") (pintype "power_in"))
      (node (ref "IC33") (pin "F9") (pinfunction "VSSQ_F9") (pintype "power_in"))
      (node (ref "IC33") (pin "G1") (pinfunction "VSSQ_G1") (pintype "power_in"))
      (node (ref "IC33") (pin "G8") (pinfunction "VSS_G8") (pintype "power_in"))
      (node (ref "IC33") (pin "G9") (pinfunction "VSSQ_G9") (pintype "power_in"))
      (node (ref "IC33") (pin "J2") (pinfunction "VSS_J2") (pintype "power_in"))
      (node (ref "IC33") (pin "J8") (pinfunction "VSS_J8") (pintype "power_in"))
      (node (ref "IC33") (pin "M1") (pinfunction "VSS_M1") (pintype "power_in"))
      (node (ref "IC33") (pin "M9") (pinfunction "VSS_M9") (pintype "power_in"))
      (node (ref "IC33") (pin "P1") (pinfunction "VSS_P1") (pintype "power_in"))
      (node (ref "IC33") (pin "P9") (pinfunction "VSS_P9") (pintype "power_in"))
      (node (ref "IC33") (pin "T1") (pinfunction "VSS_T1") (pintype "power_in"))
      (node (ref "IC33") (pin "T9") (pinfunction "VSS_T9") (pintype "power_in"))
      (node (ref "IC34") (pin "A9") (pinfunction "VSS_A9") (pintype "power_in"))
      (node (ref "IC34") (pin "B1") (pinfunction "VSSQ_B1") (pintype "power_in"))
      (node (ref "IC34") (pin "B3") (pinfunction "VSS_B3") (pintype "power_in"))
      (node (ref "IC34") (pin "B9") (pinfunction "VSSQ_B9") (pintype "power_in"))
      (node (ref "IC34") (pin "D1") (pinfunction "VSSQ_D1") (pintype "power_in"))
      (node (ref "IC34") (pin "D8") (pinfunction "VSSQ_D8") (pintype "power_in"))
      (node (ref "IC34") (pin "E1") (pinfunction "VSS_E1") (pintype "power_in"))
      (node (ref "IC34") (pin "E2") (pinfunction "VSSQ_E2") (pintype "power_in"))
      (node (ref "IC34") (pin "E8") (pinfunction "VSSQ_E8") (pintype "power_in"))
      (node (ref "IC34") (pin "F9") (pinfunction "VSSQ_F9") (pintype "power_in"))
      (node (ref "IC34") (pin "G1") (pinfunction "VSSQ_G1") (pintype "power_in"))
      (node (ref "IC34") (pin "G8") (pinfunction "VSS_G8") (pintype "power_in"))
      (node (ref "IC34") (pin "G9") (pinfunction "VSSQ_G9") (pintype "power_in"))
      (node (ref "IC34") (pin "J2") (pinfunction "VSS_J2") (pintype "power_in"))
      (node (ref "IC34") (pin "J8") (pinfunction "VSS_J8") (pintype "power_in"))
      (node (ref "IC34") (pin "M1") (pinfunction "VSS_M1") (pintype "power_in"))
      (node (ref "IC34") (pin "M9") (pinfunction "VSS_M9") (pintype "power_in"))
      (node (ref "IC34") (pin "P1") (pinfunction "VSS_P1") (pintype "power_in"))
      (node (ref "IC34") (pin "P9") (pinfunction "VSS_P9") (pintype "power_in"))
      (node (ref "IC34") (pin "T1") (pinfunction "VSS_T1") (pintype "power_in"))
      (node (ref "IC34") (pin "T9") (pinfunction "VSS_T9") (pintype "power_in"))
      (node (ref "R193") (pin "2") (pinfunction "2_2") (pintype "passive"))
      (node (ref "R196") (pin "2") (pinfunction "2_2") (pintype "passive"))
      (node (ref "R198") (pin "2") (pinfunction "2_2") (pintype "passive"))
    )
    (net (code "79") (name "VCC1P5") (class "Default")
      (node (ref "C536") (pin "1") (pinfunction "1_1") (pintype "passive"))
      (node (ref "C537") (pin "1") (pinfunction "1_1") (pintype "passive"))
      (node (ref "C538") (pin "1") (pinfunction "1_1") (pintype "passive"))
      (node (ref "C539") (pin "1") (pinfunction "1_1") (pintype "passive"))
      (node (ref "C540") (pin "1") (pinfunction "1_1") (pintype "passive"))
      (node (ref "C541") (pin "1") (pinfunction "1_1") (pintype "passive"))
      (node (ref "C542") (pin "1") (pinfunction "1_1") (pintype "passive"))
      (node (ref "C543") (pin "1") (pinfunction "1_1") (pintype "passive"))
      (node (ref "C545") (pin "1") (pinfunction "1_1") (pintype "passive"))
      (node (ref "C546") (pin "1") (pinfunction "1_1") (pintype "passive"))
      (node (ref "C547") (pin "1") (pinfunction "1_1") (pintype "passive"))
      (node (ref "C548") (pin "1") (pinfunction "1_1") (pintype "passive"))
      (node (ref "C549") (pin "1") (pinfunction "1_1") (pintype "passive"))
      (node (ref "C550") (pin "1") (pinfunction "1_1") (pintype "passive"))
      (node (ref "C551") (pin "1") (pinfunction "1_1") (pintype "passive"))
      (node (ref "C552") (pin "1") (pinfunction "1_1") (pintype "passive"))
      (node (ref "C554") (pin "1") (pinfunction "1_1") (pintype "passive"))
      (node (ref "C555") (pin "1") (pinfunction "1_1") (pintype "passive"))
      (node (ref "C557") (pin "2") (pinfunction "2_2") (pintype "passive"))
      (node (ref "C558") (pin "2") (pinfunction "2_2") (pintype "passive"))
      (node (ref "C559") (pin "1") (pinfunction "1_1") (pintype "passive"))
      (node (ref "C560") (pin "2") (pinfunction "2_2") (pintype "passive"))
      (node (ref "C562") (pin "2") (pinfunction "2_2") (pintype "passive"))
      (node (ref "C563") (pin "1") (pinfunction "1_1") (pintype "passive"))
      (node (ref "C564") (pin "1") (pinfunction "1_1") (pintype "passive"))
      (node (ref "C565") (pin "1") (pinfunction "1_1") (pintype "passive"))
      (node (ref "C566") (pin "1") (pinfunction "1_1") (pintype "passive"))
      (node (ref "C567") (pin "1") (pinfunction "1_1") (pintype "passive"))
      (node (ref "C568") (pin "1") (pinfunction "1_1") (pintype "passive"))
      (node (ref "C569") (pin "1") (pinfunction "1_1") (pintype "passive"))
      (node (ref "C570") (pin "1") (pinfunction "1_1") (pintype "passive"))
      (node (ref "C571") (pin "1") (pinfunction "1_1") (pintype "passive"))
      (node (ref "C572") (pin "1") (pinfunction "1_1") (pintype "passive"))
      (node (ref "C573") (pin "1") (pinfunction "1_1") (pintype "passive"))
      (node (ref "C574") (pin "1") (pinfunction "1_1") (pintype "passive"))
      (node (ref "C575") (pin "1") (pinfunction "1_1") (pintype "passive"))
      (node (ref "C576") (pin "1") (pinfunction "1_1") (pintype "passive"))
      (node (ref "C577") (pin "1") (pinfunction "1_1") (pintype "passive"))
      (node (ref "C578") (pin "1") (pinfunction "1_1") (pintype "passive"))
      (node (ref "C579") (pin "1") (pinfunction "1_1") (pintype "passive"))
      (node (ref "C580") (pin "1") (pinfunction "1_1") (pintype "passive"))
      (node (ref "C582") (pin "2") (pinfunction "2_2") (pintype "passive"))
      (node (ref "C583") (pin "2") (pinfunction "2_2") (pintype "passive"))
      (node (ref "C584") (pin "1") (pinfunction "1_1") (pintype "passive"))
      (node (ref "C585") (pin "2") (pinfunction "2_2") (pintype "passive"))
      (node (ref "IC33") (pin "A1") (pinfunction "VDDQ_A1") (pintype "power_in"))
      (node (ref "IC33") (pin "A8") (pinfunction "VDDQ_A8") (pintype "power_in"))
      (node (ref "IC33") (pin "B2") (pinfunction "VDD_B2") (pintype "power_in"))
      (node (ref "IC33") (pin "C1") (pinfunction "VDDQ_C1") (pintype "power_in"))
      (node (ref "IC33") (pin "C9") (pinfunction "VDDQ_C9") (pintype "power_in"))
      (node (ref "IC33") (pin "D2") (pinfunction "VDDQ_D2") (pintype "power_in"))
      (node (ref "IC33") (pin "D9") (pinfunction "VDD_D9") (pintype "power_in"))
      (node (ref "IC33") (pin "E9") (pinfunction "VDDQ_E9") (pintype "power_in"))
      (node (ref "IC33") (pin "F1") (pinfunction "VDDQ_F1") (pintype "power_in"))
      (node (ref "IC33") (pin "G7") (pinfunction "VDD_G7") (pintype "power_in"))
      (node (ref "IC33") (pin "H2") (pinfunction "VDDQ_H2") (pintype "power_in"))
      (node (ref "IC33") (pin "H9") (pinfunction "VDDQ_H9") (pintype "power_in"))
      (node (ref "IC33") (pin "K2") (pinfunction "VDD_K2") (pintype "power_in"))
      (node (ref "IC33") (pin "K8") (pinfunction "VDD_K8") (pintype "power_in"))
      (node (ref "IC33") (pin "N1") (pinfunction "VDD_N1") (pintype "power_in"))
      (node (ref "IC33") (pin "N9") (pinfunction "VDD_N9") (pintype "power_in"))
      (node (ref "IC33") (pin "R1") (pinfunction "VDD_R1") (pintype "power_in"))
      (node (ref "IC33") (pin "R9") (pinfunction "VDD_R9") (pintype "power_in"))
      (node (ref "IC34") (pin "A1") (pinfunction "VDDQ_A1") (pintype "power_in"))
      (node (ref "IC34") (pin "A8") (pinfunction "VDDQ_A8") (pintype "power_in"))
      (node (ref "IC34") (pin "B2") (pinfunction "VDD_B2") (pintype "power_in"))
      (node (ref "IC34") (pin "C1") (pinfunction "VDDQ_C1") (pintype "power_in"))
      (node (ref "IC34") (pin "C9") (pinfunction "VDDQ_C9") (pintype "power_in"))
      (node (ref "IC34") (pin "D2") (pinfunction "VDDQ_D2") (pintype "power_in"))
      (node (ref "IC34") (pin "D9") (pinfunction "VDD_D9") (pintype "power_in"))
      (node (ref "IC34") (pin "E9") (pinfunction "VDDQ_E9") (pintype "power_in"))
      (node (ref "IC34") (pin "F1") (pinfunction "VDDQ_F1") (pintype "power_in"))
      (node (ref "IC34") (pin "G7") (pinfunction "VDD_G7") (pintype "power_in"))
      (node (ref "IC34") (pin "H2") (pinfunction "VDDQ_H2") (pintype "power_in"))
      (node (ref "IC34") (pin "H9") (pinfunction "VDDQ_H9") (pintype "power_in"))
      (node (ref "IC34") (pin "K2") (pinfunction "VDD_K2") (pintype "power_in"))
      (node (ref "IC34") (pin "K8") (pinfunction "VDD_K8") (pintype "power_in"))
      (node (ref "IC34") (pin "N1") (pinfunction "VDD_N1") (pintype "power_in"))
      (node (ref "IC34") (pin "N9") (pinfunction "VDD_N9") (pintype "power_in"))
      (node (ref "IC34") (pin "R1") (pinfunction "VDD_R1") (pintype "power_in"))
      (node (ref "IC34") (pin "R9") (pinfunction "VDD_R9") (pintype "power_in"))
    )
    (net (code "80") (name "VTT_DDR3_TOP") (class "Default")
      (node (ref "C544") (pin "1") (pinfunction "1_1") (pintype "passive"))
      (node (ref "C544") (pin "2") (pinfunction "2_2") (pintype "passive"))
      (node (ref "C544") (pin "3") (pinfunction "3_3") (pintype "passive"))
      (node (ref "C544") (pin "4") (pinfunction "4_4") (pintype "passive"))
      (node (ref "C553") (pin "1") (pinfunction "1_1") (pintype "passive"))
      (node (ref "C553") (pin "2") (pinfunction "2_2") (pintype "passive"))
      (node (ref "C553") (pin "3") (pinfunction "3_3") (pintype "passive"))
      (node (ref "C553") (pin "4") (pinfunction "4_4") (pintype "passive"))
      (node (ref "C561") (pin "1") (pinfunction "1_1") (pintype "passive"))
      (node (ref "C561") (pin "2") (pinfunction "2_2") (pintype "passive"))
      (node (ref "C561") (pin "3") (pinfunction "3_3") (pintype "passive"))
      (node (ref "C561") (pin "4") (pinfunction "4_4") (pintype "passive"))
      (node (ref "R192") (pin "10") (pinfunction "10_10") (pintype "passive"))
      (node (ref "R192") (pin "11") (pinfunction "11_11") (pintype "passive"))
      (node (ref "R192") (pin "12") (pinfunction "12_12") (pintype "passive"))
      (node (ref "R192") (pin "13") (pinfunction "13_13") (pintype "passive"))
      (node (ref "R192") (pin "14") (pinfunction "14_14") (pintype "passive"))
      (node (ref "R192") (pin "15") (pinfunction "15_15") (pintype "passive"))
      (node (ref "R192") (pin "16") (pinfunction "16_16") (pintype "passive"))
      (node (ref "R192") (pin "9") (pinfunction "9_9") (pintype "passive"))
      (node (ref "R195") (pin "10") (pinfunction "10_10") (pintype "passive"))
      (node (ref "R195") (pin "11") (pinfunction "11_11") (pintype "passive"))
      (node (ref "R195") (pin "12") (pinfunction "12_12") (pintype "passive"))
      (node (ref "R195") (pin "13") (pinfunction "13_13") (pintype "passive"))
      (node (ref "R195") (pin "14") (pinfunction "14_14") (pintype "passive"))
      (node (ref "R195") (pin "15") (pinfunction "15_15") (pintype "passive"))
      (node (ref "R195") (pin "16") (pinfunction "16_16") (pintype "passive"))
      (node (ref "R195") (pin "9") (pinfunction "9_9") (pintype "passive"))
      (node (ref "R197") (pin "10") (pinfunction "10_10") (pintype "passive"))
      (node (ref "R197") (pin "11") (pinfunction "11_11") (pintype "passive"))
      (node (ref "R197") (pin "12") (pinfunction "12_12") (pintype "passive"))
      (node (ref "R197") (pin "13") (pinfunction "13_13") (pintype "passive"))
      (node (ref "R197") (pin "14") (pinfunction "14_14") (pintype "passive"))
      (node (ref "R197") (pin "15") (pinfunction "15_15") (pintype "passive"))
      (node (ref "R197") (pin "16") (pinfunction "16_16") (pintype "passive"))
      (node (ref "R197") (pin "9") (pinfunction "9_9") (pintype "passive"))
    )
    (net (code "81") (name "unconnected-(IC33B-NC-PadJ1)") (class "Default")
      (node (ref "IC33") (pin "J1") (pinfunction "NC_J1") (pintype "passive+no_connect"))
    )
    (net (code "82") (name "unconnected-(IC33B-NC-PadJ9)") (class "Default")
      (node (ref "IC33") (pin "J9") (pinfunction "NC_J9") (pintype "passive+no_connect"))
    )
    (net (code "83") (name "unconnected-(IC33B-NC-PadL1)") (class "Default")
      (node (ref "IC33") (pin "L1") (pinfunction "NC_L1") (pintype "passive+no_connect"))
    )
    (net (code "84") (name "unconnected-(IC33B-NC-PadL9)") (class "Default")
      (node (ref "IC33") (pin "L9") (pinfunction "NC_L9") (pintype "passive+no_connect"))
    )
    (net (code "85") (name "unconnected-(IC33B-NC-PadM7)") (class "Default")
      (node (ref "IC33") (pin "M7") (pinfunction "NC_M7") (pintype "passive+no_connect"))
    )
    (net (code "86") (name "unconnected-(IC33B-NC-PadT7)") (class "Default")
      (node (ref "IC33") (pin "T7") (pinfunction "NC_T7") (pintype "passive+no_connect"))
    )
    (net (code "87") (name "unconnected-(IC34B-NC-PadJ1)") (class "Default")
      (node (ref "IC34") (pin "J1") (pinfunction "NC_J1") (pintype "passive+no_connect"))
    )
    (net (code "88") (name "unconnected-(IC34B-NC-PadJ9)") (class "Default")
      (node (ref "IC34") (pin "J9") (pinfunction "NC_J9") (pintype "passive+no_connect"))
    )
    (net (code "89") (name "unconnected-(IC34B-NC-PadL1)") (class "Default")
      (node (ref "IC34") (pin "L1") (pinfunction "NC_L1") (pintype "passive+no_connect"))
    )
    (net (code "90") (name "unconnected-(IC34B-NC-PadL9)") (class "Default")
      (node (ref "IC34") (pin "L9") (pinfunction "NC_L9") (pintype "passive+no_connect"))
    )
    (net (code "91") (name "unconnected-(IC34B-NC-PadM7)") (class "Default")
      (node (ref "IC34") (pin "M7") (pinfunction "NC_M7") (pintype "passive+no_connect"))
    )
    (net (code "92") (name "unconnected-(IC34B-NC-PadT7)") (class "Default")
      (node (ref "IC34") (pin "T7") (pinfunction "NC_T7") (pintype "passive+no_connect"))
    )
    (net (code "93") (name "unconnected-(R197-Pad6)") (class "Default")
      (node (ref "R197") (pin "6") (pinfunction "6_6") (pintype "passive+no_connect"))
    )
  )
)
